# sb-sonata-lcd.net
KiCad netlist of a schematic drawn in Altium Designer
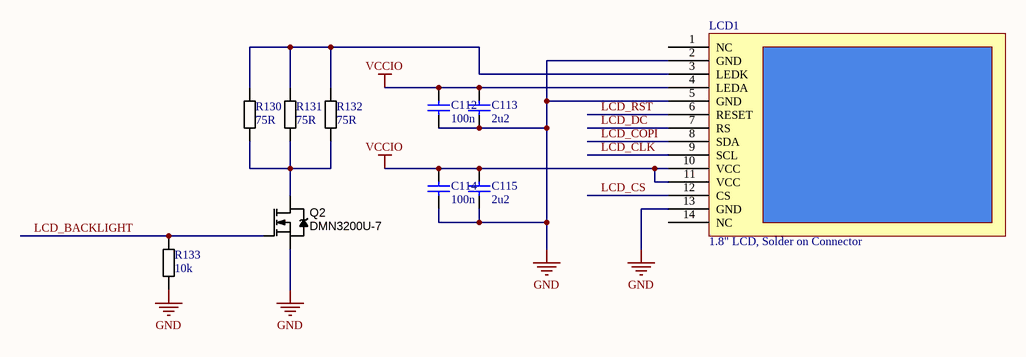
[diagram p0: sb-sonata-lcd.SchDoc]

(export (version "E")
  (design (tool "Eeschema 10.0.6"))
  (components
    (comp (ref "C112")
      (value "100n")
      (footprint "CAPC0402_M")
      (description "100n, 0402")
      (fields (field (name "PART NUMBER") "CCHIP-100n-0402"))
      (libsource (lib "NewAE_AltiumLib") (part "CAP"))
    )
    (comp (ref "C113")
      (value "2u2")
      (footprint "CAPC0603_M")
      (description "2u2, 0603")
      (fields (field (name "PART NUMBER") "CCHIP-2u2-0603-16V"))
      (libsource (lib "NewAE_AltiumLib") (part "CAP"))
    )
    (comp (ref "C114")
      (value "100n")
      (footprint "CAPC0402_M")
      (description "100n, 0402")
      (fields (field (name "PART NUMBER") "CCHIP-100n-0402"))
      (libsource (lib "NewAE_AltiumLib") (part "CAP"))
    )
    (comp (ref "C115")
      (value "2u2")
      (footprint "CAPC0603_M")
      (description "2u2, 0603")
      (fields (field (name "PART NUMBER") "CCHIP-2u2-0603-16V"))
      (libsource (lib "NewAE_AltiumLib") (part "CAP"))
    )
    (comp (ref "LCD1")
      (value "1.8\" LCD, Solder on Connector")
      (footprint "ADAFRUIT618")
      (fields (field (name "PART NUMBER") "LCD1.8INCH_ADAFRUIT618"))
      (libsource (lib "NewAE_AltiumLib") (part "LCD14Pins_Adafruit618"))
    )
    (comp (ref "Q2")
      (value "DMN3200U-7")
      (footprint "SOT95P245X110-3M")
      (description "MOSFET N-CH 30V 2.2A SOT23-3")
      (libsource (lib "NewAE_AltiumLib") (part "MOSFET_N_GSD"))
    )
    (comp (ref "R130")
      (value "75R")
      (footprint "RESC2012X70N")
      (description "75R res, 0805, 1%, 1/8W")
      (fields (field (name "PART NUMBER") "RCHIP-75R-0805") (field (name "TOLERANCE") "1%"))
      (libsource (lib "NewAE_AltiumLib") (part "RES-EU"))
    )
    (comp (ref "R131")
      (value "75R")
      (footprint "RESC2012X70N")
      (description "75R res, 0805, 1%, 1/8W")
      (fields (field (name "PART NUMBER") "RCHIP-75R-0805") (field (name "TOLERANCE") "1%"))
      (libsource (lib "NewAE_AltiumLib") (part "RES-EU"))
    )
    (comp (ref "R132")
      (value "75R")
      (footprint "RESC2012X70N")
      (description "75R res, 0805, 1%, 1/8W")
      (fields (field (name "PART NUMBER") "RCHIP-75R-0805") (field (name "TOLERANCE") "1%"))
      (libsource (lib "NewAE_AltiumLib") (part "RES-EU"))
    )
    (comp (ref "R133")
      (value "10k")
      (footprint "RESC1005X40N")
      (description "10k res, 0402, 1%, 1/16W")
      (fields (field (name "PART NUMBER") "RCHIP-10K-0402") (field (name "TOLERANCE") "1%"))
      (libsource (lib "NewAE_AltiumLib") (part "RES-EU"))
    )
  )
  (nets
    (net (code "1") (name "/LCD_BACKLIGHT") (class "Default")
      (node (ref "Q2") (pin "1") (pinfunction "G_1") (pintype "passive"))
      (node (ref "R133") (pin "1") (pinfunction "1_1") (pintype "passive"))
    )
    (net (code "2") (name "/LCD_CLK") (class "Default")
      (node (ref "LCD1") (pin "9") (pinfunction "SCL_9") (pintype "passive"))
    )
    (net (code "3") (name "/LCD_COPI") (class "Default")
      (node (ref "LCD1") (pin "8") (pinfunction "SDA_8") (pintype "passive"))
    )
    (net (code "4") (name "/LCD_CS") (class "Default")
      (node (ref "LCD1") (pin "12") (pinfunction "CS_12") (pintype "passive"))
    )
    (net (code "5") (name "/LCD_DC") (class "Default")
      (node (ref "LCD1") (pin "7") (pinfunction "RS_7") (pintype "passive"))
    )
    (net (code "6") (name "/LCD_RST") (class "Default")
      (node (ref "LCD1") (pin "6") (pinfunction "RESET_6") (pintype "passive"))
    )
    (net (code "7") (name "GND") (class "Default")
      (node (ref "C112") (pin "2") (pinfunction "2_2") (pintype "passive"))
      (node (ref "C113") (pin "2") (pinfunction "2_2") (pintype "passive"))
      (node (ref "C114") (pin "2") (pinfunction "2_2") (pintype "passive"))
      (node (ref "C115") (pin "2") (pinfunction "2_2") (pintype "passive"))
      (node (ref "LCD1") (pin "13") (pinfunction "GND_13") (pintype "passive"))
      (node (ref "LCD1") (pin "2") (pinfunction "GND_2") (pintype "passive"))
      (node (ref "LCD1") (pin "5") (pinfunction "GND_5") (pintype "passive"))
      (node (ref "Q2") (pin "2") (pinfunction "S_2") (pintype "passive"))
      (node (ref "R133") (pin "2") (pinfunction "2_2") (pintype "passive"))
    )
    (net (code "8") (name "Net-(LCD1-LEDK)") (class "Default")
      (node (ref "LCD1") (pin "3") (pinfunction "LEDK_3") (pintype "passive"))
      (node (ref "R130") (pin "1") (pinfunction "1_1") (pintype "passive"))
      (node (ref "R131") (pin "1") (pinfunction "1_1") (pintype "passive"))
      (node (ref "R132") (pin "1") (pinfunction "1_1") (pintype "passive"))
    )
    (net (code "9") (name "Net-(Q2-D)") (class "Default")
      (node (ref "Q2") (pin "3") (pinfunction "D_3") (pintype "passive"))
      (node (ref "R130") (pin "2") (pinfunction "2_2") (pintype "passive"))
      (node (ref "R131") (pin "2") (pinfunction "2_2") (pintype "passive"))
      (node (ref "R132") (pin "2") (pinfunction "2_2") (pintype "passive"))
    )
    (net (code "10") (name "VCCIO") (class "Default")
      (node (ref "C112") (pin "1") (pinfunction "1_1") (pintype "passive"))
      (node (ref "C113") (pin "1") (pinfunction "1_1") (pintype "passive"))
      (node (ref "C114") (pin "1") (pinfunction "1_1") (pintype "passive"))
      (node (ref "C115") (pin "1") (pinfunction "1_1") (pintype "passive"))
      (node (ref "LCD1") (pin "10") (pinfunction "VCC_10") (pintype "passive"))
      (node (ref "LCD1") (pin "11") (pinfunction "VCC_11") (pintype "passive"))
      (node (ref "LCD1") (pin "4") (pinfunction "LEDA_4") (pintype "passive"))
    )
    (net (code "11") (name "unconnected-(LCD1-NC-Pad1)") (class "Default")
      (node (ref "LCD1") (pin "1") (pinfunction "NC_1") (pintype "passive"))
    )
    (net (code "12") (name "unconnected-(LCD1-NC-Pad14)") (class "Default")
      (node (ref "LCD1") (pin "14") (pinfunction "NC_14") (pintype "passive"))
    )
  )
)
